# USB2514_USB_PORTS.net
KiCad netlist of a schematic drawn in Altium Designer
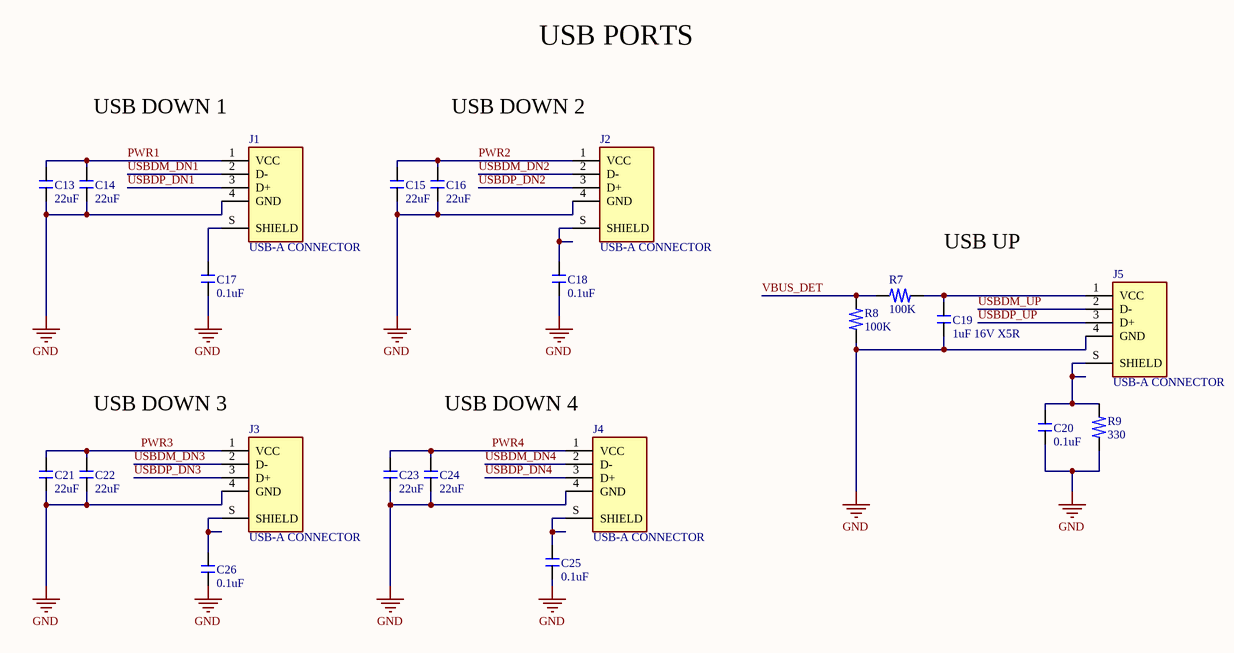
[diagram p0: USB2514 USB PORTS.SchDoc]

(export (version "E")
  (design (tool "Eeschema 10.0.6"))
  (components
    (comp (ref "C13")
      (value "22uF")
      (footprint "CAPC3216X10N-1206")
      (libsource (lib "SCH_LIB") (part "CAP_1206_22uF"))
    )
    (comp (ref "C14")
      (value "22uF")
      (footprint "CAPC3216X10N-1206")
      (libsource (lib "SCH_LIB") (part "CAP_1206_22uF"))
    )
    (comp (ref "C15")
      (value "22uF")
      (footprint "CAPC3216X10N-1206")
      (libsource (lib "SCH_LIB") (part "CAP_1206_22uF"))
    )
    (comp (ref "C16")
      (value "22uF")
      (footprint "CAPC3216X10N-1206")
      (libsource (lib "SCH_LIB") (part "CAP_1206_22uF"))
    )
    (comp (ref "C17")
      (value "0.1uF")
      (footprint "CAPC1608X06N-0603")
      (libsource (lib "SCH_LIB") (part "CAP_0603_0.1uF"))
    )
    (comp (ref "C18")
      (value "0.1uF")
      (footprint "CAPC1608X06N-0603")
      (libsource (lib "SCH_LIB") (part "CAP_0603_0.1uF"))
    )
    (comp (ref "C19")
      (value "1uF 16V X5R")
      (footprint "CAPC1608X06N-0603")
      (libsource (lib "SCH_LIB") (part "CAP_0603_0.1uF"))
    )
    (comp (ref "C20")
      (value "0.1uF")
      (footprint "CAPC1608X06N-0603")
      (libsource (lib "SCH_LIB") (part "CAP_0603_0.1uF"))
    )
    (comp (ref "C21")
      (value "22uF")
      (footprint "CAPC3216X10N-1206")
      (libsource (lib "SCH_LIB") (part "CAP_1206_22uF"))
    )
    (comp (ref "C22")
      (value "22uF")
      (footprint "CAPC3216X10N-1206")
      (libsource (lib "SCH_LIB") (part "CAP_1206_22uF"))
    )
    (comp (ref "C23")
      (value "22uF")
      (footprint "CAPC3216X10N-1206")
      (libsource (lib "SCH_LIB") (part "CAP_1206_22uF"))
    )
    (comp (ref "C24")
      (value "22uF")
      (footprint "CAPC3216X10N-1206")
      (libsource (lib "SCH_LIB") (part "CAP_1206_22uF"))
    )
    (comp (ref "C25")
      (value "0.1uF")
      (footprint "CAPC1608X06N-0603")
      (libsource (lib "SCH_LIB") (part "CAP_0603_0.1uF"))
    )
    (comp (ref "C26")
      (value "0.1uF")
      (footprint "CAPC1608X06N-0603")
      (libsource (lib "SCH_LIB") (part "CAP_0603_0.1uF"))
    )
    (comp (ref "J1")
      (value "USB-A CONNECTOR")
      (footprint "USB-U-A-24DS-Y-1")
      (description "USB-A (USB TYPE-A) USB 2.0")
      (fields (field (name "MF") "Samtec") (field (name "MP") "USB-A-S-X-X-VU"))
      (libsource (lib "SCH_LIB") (part "USB-U-A-24DS-Y-1"))
    )
    (comp (ref "J2")
      (value "USB-A CONNECTOR")
      (footprint "USB-U-A-24DS-Y-1")
      (description "USB-A (USB TYPE-A) USB 2.0")
      (fields (field (name "MF") "Samtec") (field (name "MP") "USB-A-S-X-X-VU"))
      (libsource (lib "SCH_LIB") (part "USB-U-A-24DS-Y-1"))
    )
    (comp (ref "J3")
      (value "USB-A CONNECTOR")
      (footprint "USB-U-A-24DS-Y-1")
      (description "USB-A (USB TYPE-A) USB 2.0")
      (fields (field (name "MF") "Samtec") (field (name "MP") "USB-A-S-X-X-VU"))
      (libsource (lib "SCH_LIB") (part "USB-U-A-24DS-Y-1"))
    )
    (comp (ref "J4")
      (value "USB-A CONNECTOR")
      (footprint "USB-U-A-24DS-Y-1")
      (description "USB-A (USB TYPE-A) USB 2.0")
      (fields (field (name "MF") "Samtec") (field (name "MP") "USB-A-S-X-X-VU"))
      (libsource (lib "SCH_LIB") (part "USB-U-A-24DS-Y-1"))
    )
    (comp (ref "J5")
      (value "USB-A CONNECTOR")
      (footprint "USB-U-A-24DS-Y-1")
      (description "USB-A (USB TYPE-A) USB 2.0")
      (fields (field (name "MF") "Samtec") (field (name "MP") "USB-A-S-X-X-VU"))
      (libsource (lib "SCH_LIB") (part "USB-U-A-24DS-Y-1"))
    )
    (comp (ref "R7")
      (value "100K")
      (footprint "RESC1608X06N-0603")
      (libsource (lib "SCH_LIB") (part "RES_0603_1K"))
    )
    (comp (ref "R8")
      (value "100K")
      (footprint "RESC1608X06N-0603")
      (libsource (lib "SCH_LIB") (part "RES_0603_1K"))
    )
    (comp (ref "R9")
      (value "330")
      (footprint "RESC1608X06N-0603")
      (libsource (lib "SCH_LIB") (part "RES_0603_1K"))
    )
  )
  (nets
    (net (code "1") (name "/PWR1") (class "Default")
      (node (ref "C13") (pin "2") (pinfunction "2_2") (pintype "passive"))
      (node (ref "C14") (pin "2") (pinfunction "2_2") (pintype "passive"))
      (node (ref "J1") (pin "1") (pinfunction "VCC_1") (pintype "power_in"))
    )
    (net (code "2") (name "/PWR2") (class "Default")
      (node (ref "C15") (pin "2") (pinfunction "2_2") (pintype "passive"))
      (node (ref "C16") (pin "2") (pinfunction "2_2") (pintype "passive"))
      (node (ref "J2") (pin "1") (pinfunction "VCC_1") (pintype "power_in"))
    )
    (net (code "3") (name "/PWR3") (class "Default")
      (node (ref "C21") (pin "2") (pinfunction "2_2") (pintype "passive"))
      (node (ref "C22") (pin "2") (pinfunction "2_2") (pintype "passive"))
      (node (ref "J3") (pin "1") (pinfunction "VCC_1") (pintype "power_in"))
    )
    (net (code "4") (name "/PWR4") (class "Default")
      (node (ref "C23") (pin "2") (pinfunction "2_2") (pintype "passive"))
      (node (ref "C24") (pin "2") (pinfunction "2_2") (pintype "passive"))
      (node (ref "J4") (pin "1") (pinfunction "VCC_1") (pintype "power_in"))
    )
    (net (code "5") (name "/USBDM_DN1") (class "Default")
      (node (ref "J1") (pin "2") (pinfunction "D-_2") (pintype "passive"))
    )
    (net (code "6") (name "/USBDM_DN2") (class "Default")
      (node (ref "J2") (pin "2") (pinfunction "D-_2") (pintype "passive"))
    )
    (net (code "7") (name "/USBDM_DN3") (class "Default")
      (node (ref "J3") (pin "2") (pinfunction "D-_2") (pintype "passive"))
    )
    (net (code "8") (name "/USBDM_DN4") (class "Default")
      (node (ref "J4") (pin "2") (pinfunction "D-_2") (pintype "passive"))
    )
    (net (code "9") (name "/USBDM_UP") (class "Default")
      (node (ref "J5") (pin "2") (pinfunction "D-_2") (pintype "passive"))
    )
    (net (code "10") (name "/USBDP_DN1") (class "Default")
      (node (ref "J1") (pin "3") (pinfunction "D+_3") (pintype "passive"))
    )
    (net (code "11") (name "/USBDP_DN2") (class "Default")
      (node (ref "J2") (pin "3") (pinfunction "D+_3") (pintype "passive"))
    )
    (net (code "12") (name "/USBDP_DN3") (class "Default")
      (node (ref "J3") (pin "3") (pinfunction "D+_3") (pintype "passive"))
    )
    (net (code "13") (name "/USBDP_DN4") (class "Default")
      (node (ref "J4") (pin "3") (pinfunction "D+_3") (pintype "passive"))
    )
    (net (code "14") (name "/USBDP_UP") (class "Default")
      (node (ref "J5") (pin "3") (pinfunction "D+_3") (pintype "passive"))
    )
    (net (code "15") (name "/VBUS_DET") (class "Default")
      (node (ref "R7") (pin "1") (pinfunction "1_1") (pintype "passive"))
      (node (ref "R8") (pin "2") (pinfunction "2_2") (pintype "passive"))
    )
    (net (code "16") (name "GND") (class "Default")
      (node (ref "C13") (pin "1") (pinfunction "1_1") (pintype "passive"))
      (node (ref "C14") (pin "1") (pinfunction "1_1") (pintype "passive"))
      (node (ref "C15") (pin "1") (pinfunction "1_1") (pintype "passive"))
      (node (ref "C16") (pin "1") (pinfunction "1_1") (pintype "passive"))
      (node (ref "C17") (pin "1") (pinfunction "1_1") (pintype "passive"))
      (node (ref "C18") (pin "1") (pinfunction "1_1") (pintype "passive"))
      (node (ref "C19") (pin "1") (pinfunction "1_1") (pintype "passive"))
      (node (ref "C20") (pin "1") (pinfunction "1_1") (pintype "passive"))
      (node (ref "C21") (pin "1") (pinfunction "1_1") (pintype "passive"))
      (node (ref "C22") (pin "1") (pinfunction "1_1") (pintype "passive"))
      (node (ref "C23") (pin "1") (pinfunction "1_1") (pintype "passive"))
      (node (ref "C24") (pin "1") (pinfunction "1_1") (pintype "passive"))
      (node (ref "C25") (pin "1") (pinfunction "1_1") (pintype "passive"))
      (node (ref "C26") (pin "1") (pinfunction "1_1") (pintype "passive"))
      (node (ref "J1") (pin "4") (pinfunction "GND_4") (pintype "power_in"))
      (node (ref "J2") (pin "4") (pinfunction "GND_4") (pintype "power_in"))
      (node (ref "J3") (pin "4") (pinfunction "GND_4") (pintype "power_in"))
      (node (ref "J4") (pin "4") (pinfunction "GND_4") (pintype "power_in"))
      (node (ref "J5") (pin "4") (pinfunction "GND_4") (pintype "power_in"))
      (node (ref "R8") (pin "1") (pinfunction "1_1") (pintype "passive"))
      (node (ref "R9") (pin "1") (pinfunction "1_1") (pintype "passive"))
    )
    (net (code "17") (name "Net-(J1-SHIELD)") (class "Default")
      (node (ref "C17") (pin "2") (pinfunction "2_2") (pintype "passive"))
      (node (ref "J1") (pin "S") (pinfunction "SHIELD_S") (pintype "passive"))
    )
    (net (code "18") (name "Net-(J2-SHIELD)") (class "Default")
      (node (ref "C18") (pin "2") (pinfunction "2_2") (pintype "passive"))
      (node (ref "J2") (pin "S") (pinfunction "SHIELD_S") (pintype "passive"))
    )
    (net (code "19") (name "Net-(J3-SHIELD)") (class "Default")
      (node (ref "C26") (pin "2") (pinfunction "2_2") (pintype "passive"))
      (node (ref "J3") (pin "S") (pinfunction "SHIELD_S") (pintype "passive"))
    )
    (net (code "20") (name "Net-(J4-SHIELD)") (class "Default")
      (node (ref "C25") (pin "2") (pinfunction "2_2") (pintype "passive"))
      (node (ref "J4") (pin "S") (pinfunction "SHIELD_S") (pintype "passive"))
    )
    (net (code "21") (name "Net-(J5-SHIELD)") (class "Default")
      (node (ref "C20") (pin "2") (pinfunction "2_2") (pintype "passive"))
      (node (ref "J5") (pin "S") (pinfunction "SHIELD_S") (pintype "passive"))
      (node (ref "R9") (pin "2") (pinfunction "2_2") (pintype "passive"))
    )
    (net (code "22") (name "Net-(J5-VCC)") (class "Default")
      (node (ref "C19") (pin "2") (pinfunction "2_2") (pintype "passive"))
      (node (ref "J5") (pin "1") (pinfunction "VCC_1") (pintype "power_in"))
      (node (ref "R7") (pin "2") (pinfunction "2_2") (pintype "passive"))
    )
  )
)
